# Main.net
KiCad netlist of a schematic drawn in Altium Designer
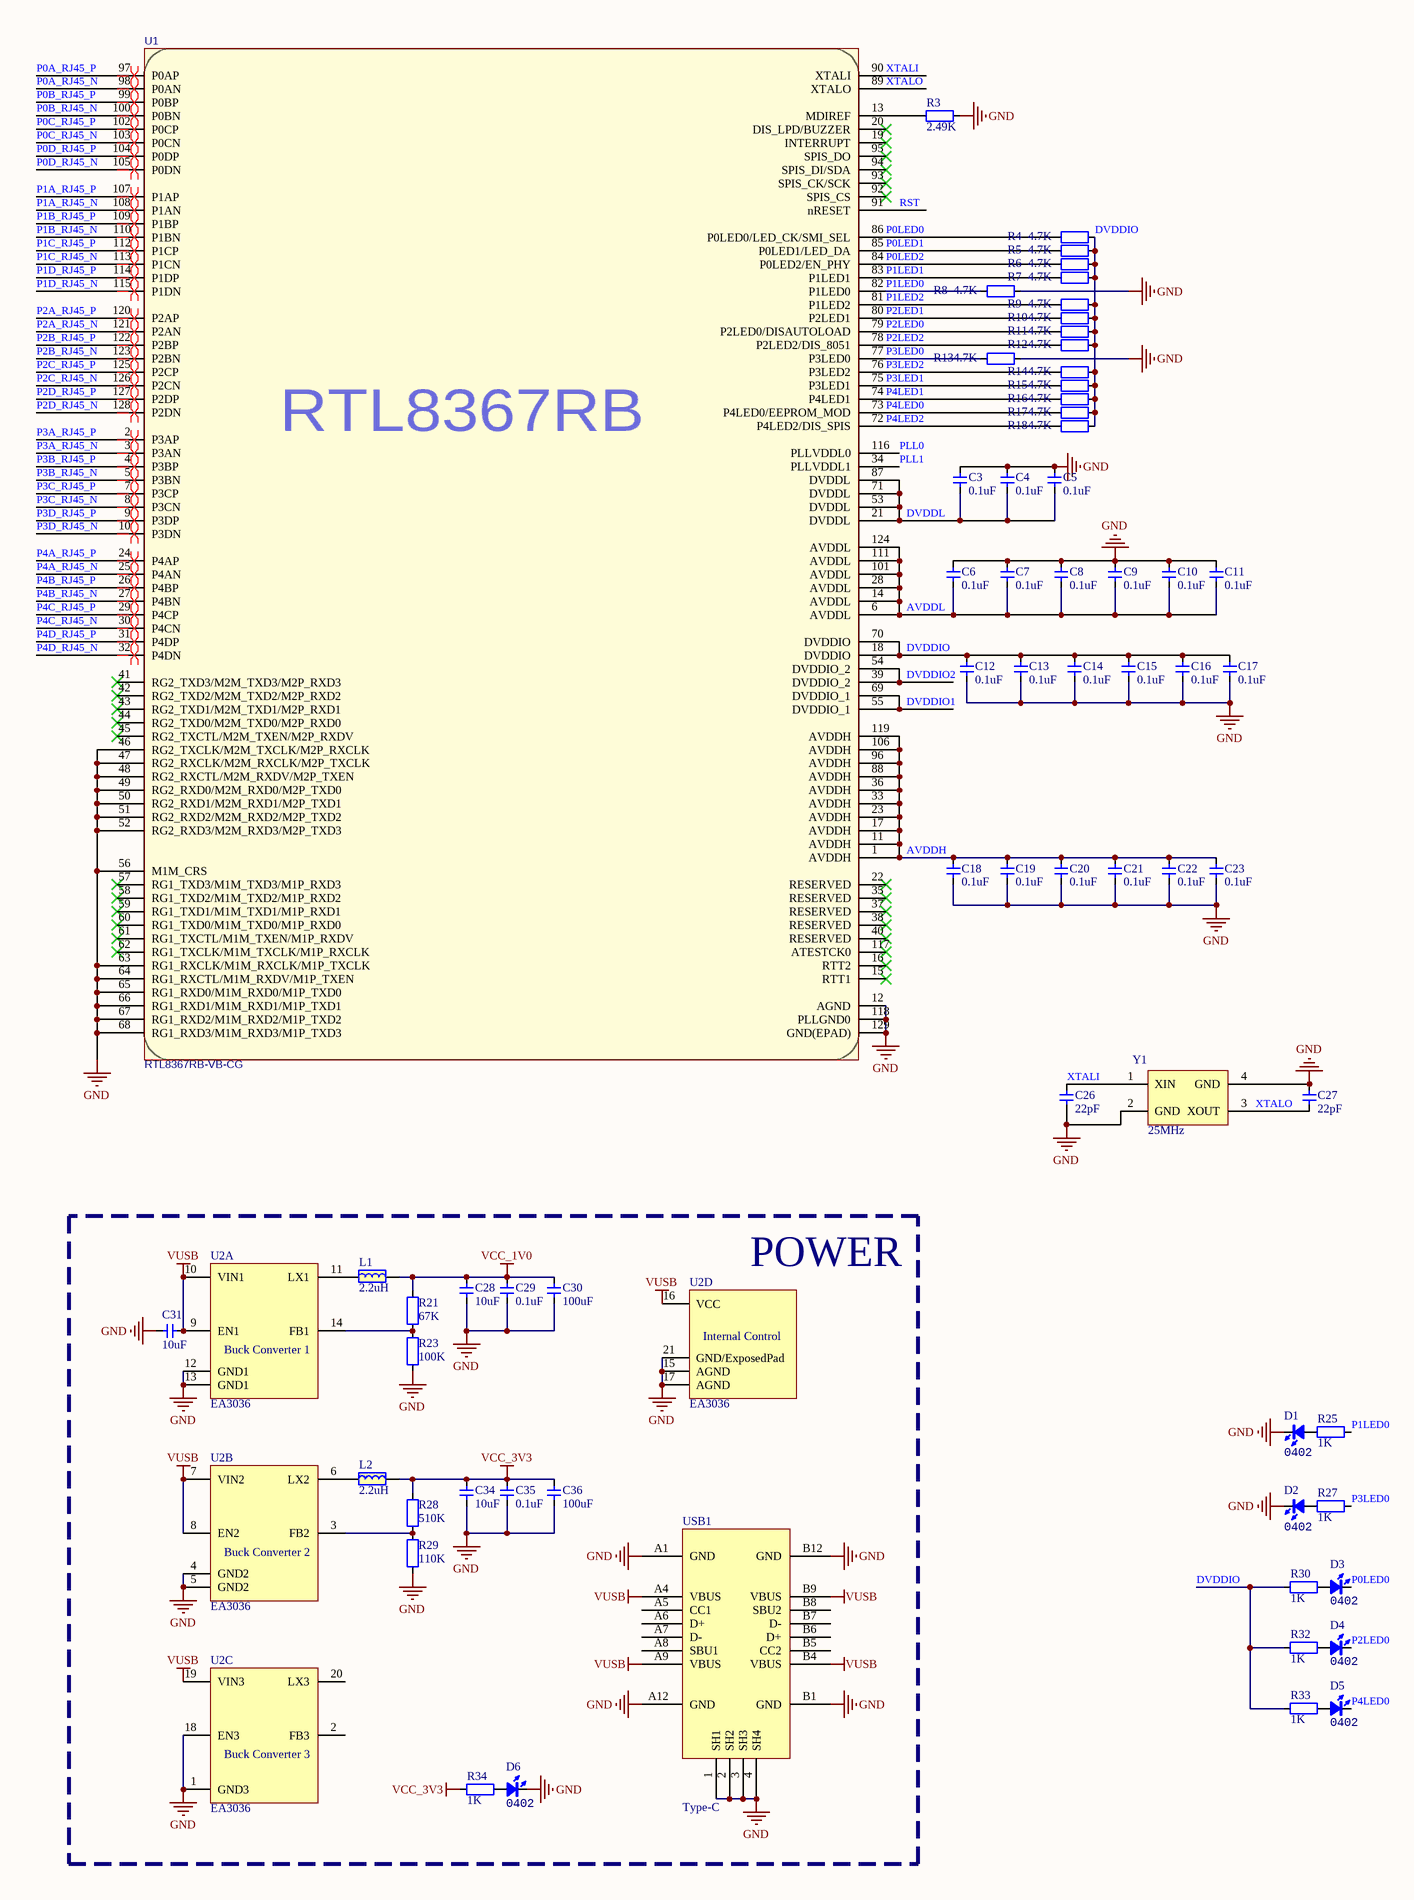
[diagram p0: Main.SchDoc, left]
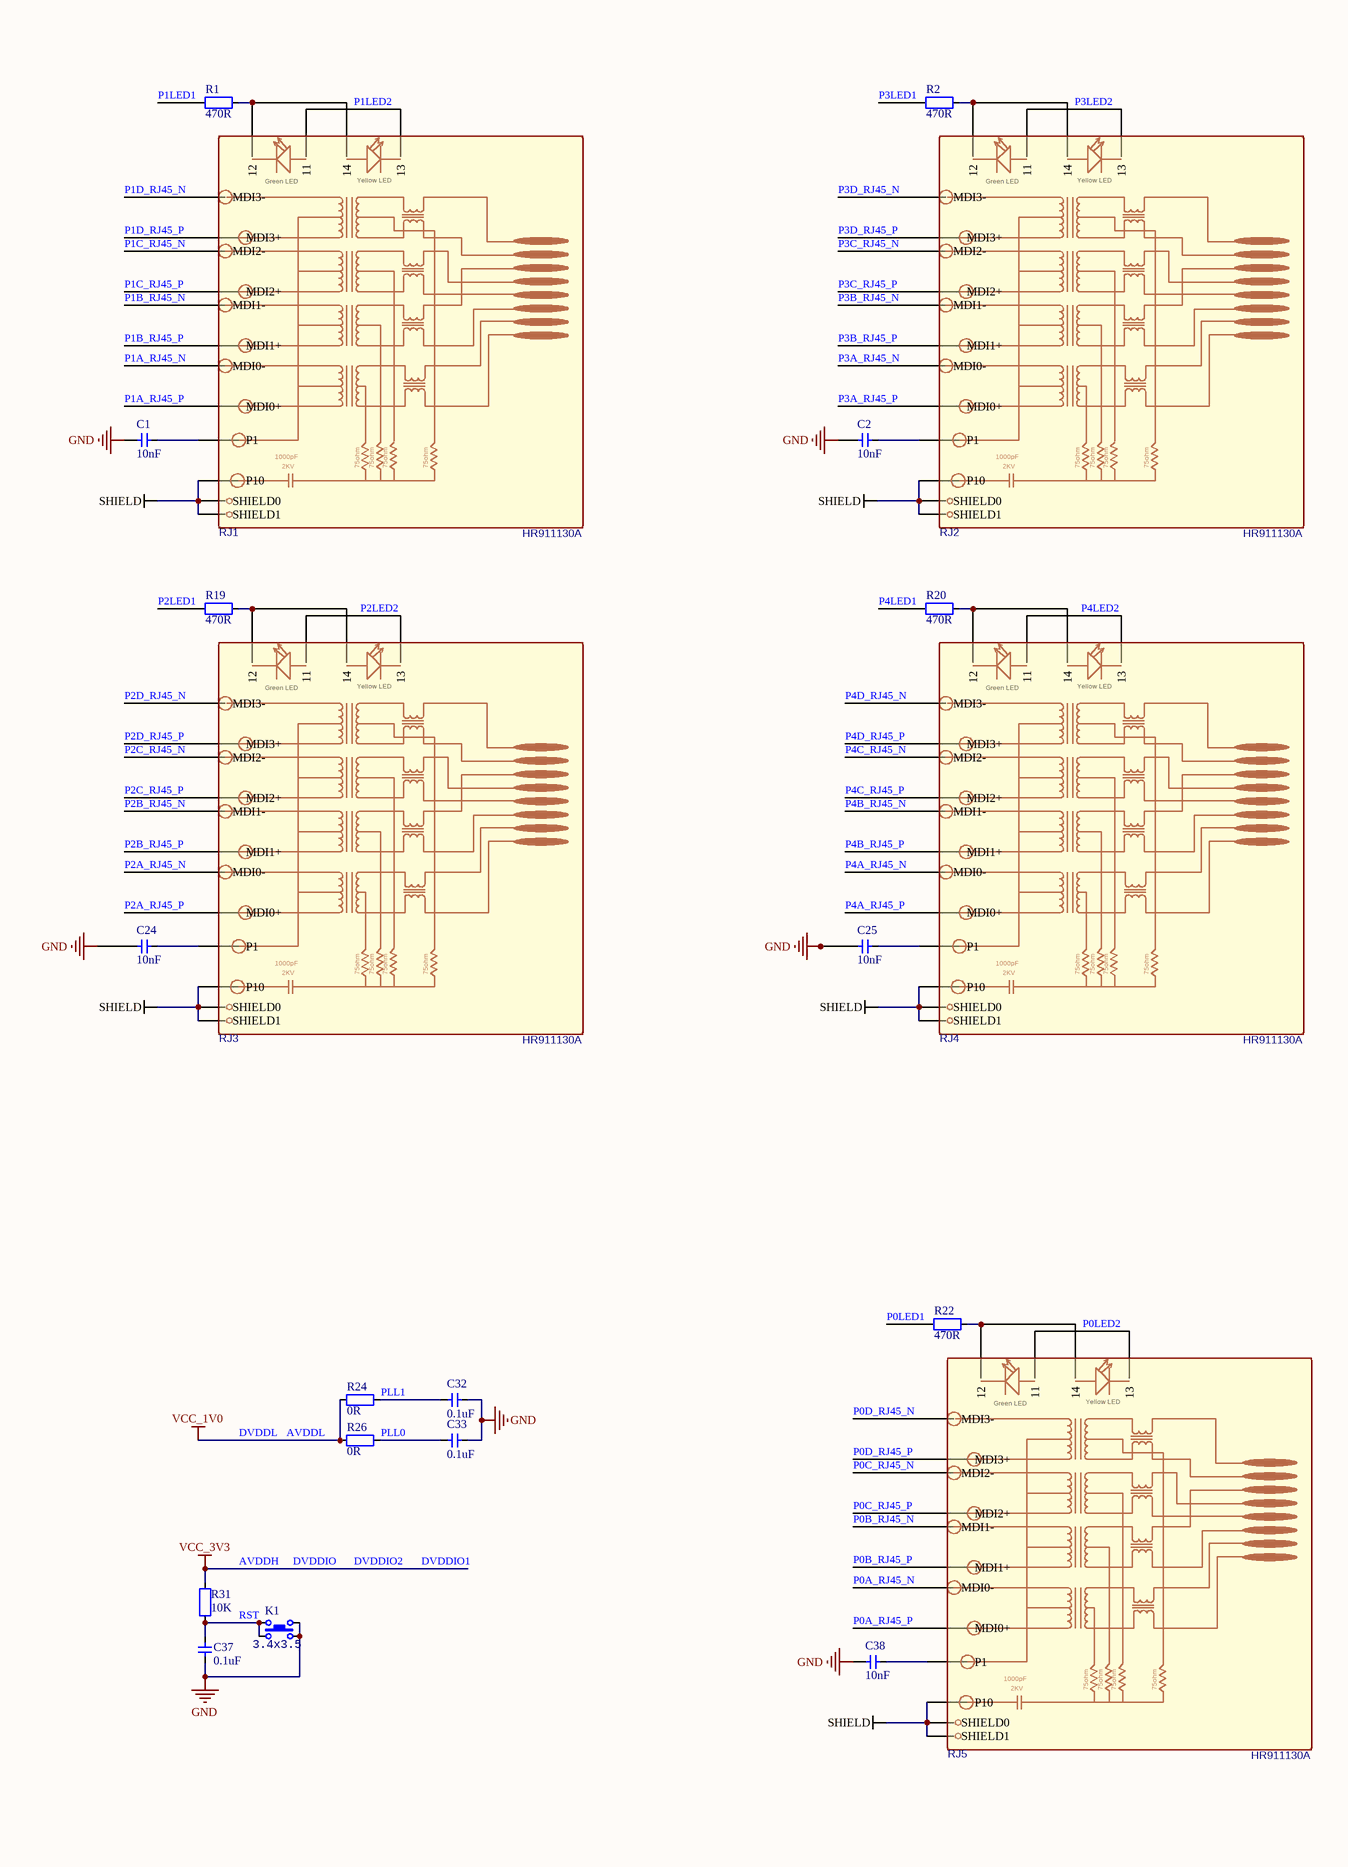
[diagram p1: Main.SchDoc, right]

(export (version "E")
  (design (tool "Eeschema 10.0.6"))
  (components
    (comp (ref "C1")
      (value "10nF")
      (footprint "CAP_0402")
      (description "Capacitor")
      (libsource (lib "MyPcbLib") (part "电容-0402"))
    )
    (comp (ref "C2")
      (value "10nF")
      (footprint "CAP_0402")
      (description "Capacitor")
      (libsource (lib "MyPcbLib") (part "电容-0402"))
    )
    (comp (ref "C3")
      (value "0.1uF")
      (footprint "CAP_0402")
      (description "Capacitor")
      (libsource (lib "MyPcbLib") (part "电容-0402"))
    )
    (comp (ref "C4")
      (value "0.1uF")
      (footprint "CAP_0402")
      (description "Capacitor")
      (libsource (lib "MyPcbLib") (part "电容-0402"))
    )
    (comp (ref "C5")
      (value "0.1uF")
      (footprint "CAP_0402")
      (description "Capacitor")
      (libsource (lib "MyPcbLib") (part "电容-0402"))
    )
    (comp (ref "C6")
      (value "0.1uF")
      (footprint "CAP_0402")
      (description "Capacitor")
      (libsource (lib "MyPcbLib") (part "电容-0402"))
    )
    (comp (ref "C7")
      (value "0.1uF")
      (footprint "CAP_0402")
      (description "Capacitor")
      (libsource (lib "MyPcbLib") (part "电容-0402"))
    )
    (comp (ref "C8")
      (value "0.1uF")
      (footprint "CAP_0402")
      (description "Capacitor")
      (libsource (lib "MyPcbLib") (part "电容-0402"))
    )
    (comp (ref "C9")
      (value "0.1uF")
      (footprint "CAP_0402")
      (description "Capacitor")
      (libsource (lib "MyPcbLib") (part "电容-0402"))
    )
    (comp (ref "C10")
      (value "0.1uF")
      (footprint "CAP_0402")
      (description "Capacitor")
      (libsource (lib "MyPcbLib") (part "电容-0402"))
    )
    (comp (ref "C11")
      (value "0.1uF")
      (footprint "CAP_0402")
      (description "Capacitor")
      (libsource (lib "MyPcbLib") (part "电容-0402"))
    )
    (comp (ref "C12")
      (value "0.1uF")
      (footprint "CAP_0402")
      (description "Capacitor")
      (libsource (lib "MyPcbLib") (part "电容-0402"))
    )
    (comp (ref "C13")
      (value "0.1uF")
      (footprint "CAP_0402")
      (description "Capacitor")
      (libsource (lib "MyPcbLib") (part "电容-0402"))
    )
    (comp (ref "C14")
      (value "0.1uF")
      (footprint "CAP_0402")
      (description "Capacitor")
      (libsource (lib "MyPcbLib") (part "电容-0402"))
    )
    (comp (ref "C15")
      (value "0.1uF")
      (footprint "CAP_0402")
      (description "Capacitor")
      (libsource (lib "MyPcbLib") (part "电容-0402"))
    )
    (comp (ref "C16")
      (value "0.1uF")
      (footprint "CAP_0402")
      (description "Capacitor")
      (libsource (lib "MyPcbLib") (part "电容-0402"))
    )
    (comp (ref "C17")
      (value "0.1uF")
      (footprint "CAP_0402")
      (description "Capacitor")
      (libsource (lib "MyPcbLib") (part "电容-0402"))
    )
    (comp (ref "C18")
      (value "0.1uF")
      (footprint "CAP_0402")
      (description "Capacitor")
      (libsource (lib "MyPcbLib") (part "电容-0402"))
    )
    (comp (ref "C19")
      (value "0.1uF")
      (footprint "CAP_0402")
      (description "Capacitor")
      (libsource (lib "MyPcbLib") (part "电容-0402"))
    )
    (comp (ref "C20")
      (value "0.1uF")
      (footprint "CAP_0402")
      (description "Capacitor")
      (libsource (lib "MyPcbLib") (part "电容-0402"))
    )
    (comp (ref "C21")
      (value "0.1uF")
      (footprint "CAP_0402")
      (description "Capacitor")
      (libsource (lib "MyPcbLib") (part "电容-0402"))
    )
    (comp (ref "C22")
      (value "0.1uF")
      (footprint "CAP_0402")
      (description "Capacitor")
      (libsource (lib "MyPcbLib") (part "电容-0402"))
    )
    (comp (ref "C23")
      (value "0.1uF")
      (footprint "CAP_0402")
      (description "Capacitor")
      (libsource (lib "MyPcbLib") (part "电容-0402"))
    )
    (comp (ref "C24")
      (value "10nF")
      (footprint "CAP_0402")
      (description "Capacitor")
      (libsource (lib "MyPcbLib") (part "电容-0402"))
    )
    (comp (ref "C25")
      (value "10nF")
      (footprint "CAP_0402")
      (description "Capacitor")
      (libsource (lib "MyPcbLib") (part "电容-0402"))
    )
    (comp (ref "C26")
      (value "22pF")
      (footprint "CAP_0402")
      (description "Capacitor")
      (libsource (lib "MyPcbLib") (part "电容-0402"))
    )
    (comp (ref "C27")
      (value "22pF")
      (footprint "CAP_0402")
      (description "Capacitor")
      (libsource (lib "MyPcbLib") (part "电容-0402"))
    )
    (comp (ref "C28")
      (value "10uF")
      (footprint "CAP_0402")
      (description "Capacitor")
      (libsource (lib "MyPcbLib") (part "电容-0402"))
    )
    (comp (ref "C29")
      (value "0.1uF")
      (footprint "CAP_0402")
      (description "Capacitor")
      (libsource (lib "MyPcbLib") (part "电容-0402"))
    )
    (comp (ref "C30")
      (value "100uF")
      (footprint "1206-CAP")
      (description "Capacitor")
      (libsource (lib "MyPcbLib") (part "电容-1206"))
    )
    (comp (ref "C31")
      (value "10uF")
      (footprint "CAP_0402")
      (description "Capacitor")
      (libsource (lib "MyPcbLib") (part "电容-0402"))
    )
    (comp (ref "C32")
      (value "0.1uF")
      (footprint "CAP_0402")
      (description "Capacitor")
      (libsource (lib "MyPcbLib") (part "电容-0402"))
    )
    (comp (ref "C33")
      (value "0.1uF")
      (footprint "CAP_0402")
      (description "Capacitor")
      (libsource (lib "MyPcbLib") (part "电容-0402"))
    )
    (comp (ref "C34")
      (value "10uF")
      (footprint "CAP_0402")
      (description "Capacitor")
      (libsource (lib "MyPcbLib") (part "电容-0402"))
    )
    (comp (ref "C35")
      (value "0.1uF")
      (footprint "CAP_0402")
      (description "Capacitor")
      (libsource (lib "MyPcbLib") (part "电容-0402"))
    )
    (comp (ref "C36")
      (value "100uF")
      (footprint "1206-CAP")
      (description "Capacitor")
      (libsource (lib "MyPcbLib") (part "电容-1206"))
    )
    (comp (ref "C37")
      (value "0.1uF")
      (footprint "CAP_0402")
      (description "Capacitor")
      (libsource (lib "MyPcbLib") (part "电容-0402"))
    )
    (comp (ref "C38")
      (value "10nF")
      (footprint "CAP_0402")
      (description "Capacitor")
      (libsource (lib "MyPcbLib") (part "电容-0402"))
    )
    (comp (ref "D1")
      (value "color?")
      (footprint "LED_0402_RED")
      (description "LED")
      (fields (field (name "TYPE") "0402"))
      (libsource (lib "KitSprout") (part "LED_0402"))
    )
    (comp (ref "D2")
      (value "color?")
      (footprint "LED_0402_RED")
      (description "LED")
      (fields (field (name "TYPE") "0402"))
      (libsource (lib "KitSprout") (part "LED_0402"))
    )
    (comp (ref "D3")
      (value "color?")
      (footprint "LED_0402_RED")
      (description "LED")
      (fields (field (name "TYPE") "0402"))
      (libsource (lib "") (part "LED_0402_1"))
    )
    (comp (ref "D4")
      (value "color?")
      (footprint "LED_0402_RED")
      (description "LED")
      (fields (field (name "TYPE") "0402"))
      (libsource (lib "") (part "LED_0402_1"))
    )
    (comp (ref "D5")
      (value "color?")
      (footprint "LED_0402_RED")
      (description "LED")
      (fields (field (name "TYPE") "0402"))
      (libsource (lib "") (part "LED_0402_1"))
    )
    (comp (ref "D6")
      (value "color?")
      (footprint "LED_0402_RED")
      (description "LED")
      (fields (field (name "TYPE") "0402"))
      (libsource (lib "") (part "LED_0402_1"))
    )
    (comp (ref "K1")
      (value "3.4x3.5")
      (footprint "ButtonTACT_3.5*3.55_90")
      (description "Button")
      (fields (field (name "Comment") "TACT 4P"))
      (libsource (lib "KitSprout") (part "ButtonTACT"))
    )
    (comp (ref "L1")
      (value "2.2uH")
      (footprint "2520-L")
      (description "磁珠")
      (libsource (lib "MyPcbLib") (part "电感-2520"))
    )
    (comp (ref "L2")
      (value "2.2uH")
      (footprint "2520-L")
      (description "磁珠")
      (libsource (lib "MyPcbLib") (part "电感-2520"))
    )
    (comp (ref "R1")
      (value "470R")
      (footprint "RES_0402")
      (description "Resistor")
      (libsource (lib "MyPcbLib") (part "电阻-0402"))
    )
    (comp (ref "R2")
      (value "470R")
      (footprint "RES_0402")
      (description "Resistor")
      (libsource (lib "MyPcbLib") (part "电阻-0402"))
    )
    (comp (ref "R3")
      (value "2.49K")
      (footprint "RES_0402")
      (description "Resistor")
      (libsource (lib "MyPcbLib") (part "电阻-0402"))
    )
    (comp (ref "R4")
      (value "4.7K")
      (footprint "RES_0402")
      (description "Resistor")
      (libsource (lib "MyPcbLib") (part "电阻-0402"))
    )
    (comp (ref "R5")
      (value "4.7K")
      (footprint "RES_0402")
      (description "Resistor")
      (libsource (lib "MyPcbLib") (part "电阻-0402"))
    )
    (comp (ref "R6")
      (value "4.7K")
      (footprint "RES_0402")
      (description "Resistor")
      (libsource (lib "MyPcbLib") (part "电阻-0402"))
    )
    (comp (ref "R7")
      (value "4.7K")
      (footprint "RES_0402")
      (description "Resistor")
      (libsource (lib "MyPcbLib") (part "电阻-0402"))
    )
    (comp (ref "R8")
      (value "4.7K")
      (footprint "RES_0402")
      (description "Resistor")
      (libsource (lib "MyPcbLib") (part "电阻-0402"))
    )
    (comp (ref "R9")
      (value "4.7K")
      (footprint "RES_0402")
      (description "Resistor")
      (libsource (lib "MyPcbLib") (part "电阻-0402"))
    )
    (comp (ref "R10")
      (value "4.7K")
      (footprint "RES_0402")
      (description "Resistor")
      (libsource (lib "MyPcbLib") (part "电阻-0402"))
    )
    (comp (ref "R11")
      (value "4.7K")
      (footprint "RES_0402")
      (description "Resistor")
      (libsource (lib "MyPcbLib") (part "电阻-0402"))
    )
    (comp (ref "R12")
      (value "4.7K")
      (footprint "RES_0402")
      (description "Resistor")
      (libsource (lib "MyPcbLib") (part "电阻-0402"))
    )
    (comp (ref "R13")
      (value "4.7K")
      (footprint "RES_0402")
      (description "Resistor")
      (libsource (lib "MyPcbLib") (part "电阻-0402"))
    )
    (comp (ref "R14")
      (value "4.7K")
      (footprint "RES_0402")
      (description "Resistor")
      (libsource (lib "MyPcbLib") (part "电阻-0402"))
    )
    (comp (ref "R15")
      (value "4.7K")
      (footprint "RES_0402")
      (description "Resistor")
      (libsource (lib "MyPcbLib") (part "电阻-0402"))
    )
    (comp (ref "R16")
      (value "4.7K")
      (footprint "RES_0402")
      (description "Resistor")
      (libsource (lib "MyPcbLib") (part "电阻-0402"))
    )
    (comp (ref "R17")
      (value "4.7K")
      (footprint "RES_0402")
      (description "Resistor")
      (libsource (lib "MyPcbLib") (part "电阻-0402"))
    )
    (comp (ref "R18")
      (value "4.7K")
      (footprint "RES_0402")
      (description "Resistor")
      (libsource (lib "MyPcbLib") (part "电阻-0402"))
    )
    (comp (ref "R19")
      (value "470R")
      (footprint "RES_0402")
      (description "Resistor")
      (libsource (lib "MyPcbLib") (part "电阻-0402"))
    )
    (comp (ref "R20")
      (value "470R")
      (footprint "RES_0402")
      (description "Resistor")
      (libsource (lib "MyPcbLib") (part "电阻-0402"))
    )
    (comp (ref "R21")
      (value "67K")
      (footprint "RES_0402")
      (description "Resistor")
      (libsource (lib "") (part "电阻-0402_2"))
    )
    (comp (ref "R22")
      (value "470R")
      (footprint "RES_0402")
      (description "Resistor")
      (libsource (lib "MyPcbLib") (part "电阻-0402"))
    )
    (comp (ref "R23")
      (value "100K")
      (footprint "RES_0402")
      (description "Resistor")
      (libsource (lib "") (part "电阻-0402_2"))
    )
    (comp (ref "R24")
      (value "0R")
      (footprint "RES_0402")
      (description "Resistor")
      (libsource (lib "") (part "电阻-0402_1"))
    )
    (comp (ref "R25")
      (value "1K")
      (footprint "RES_0402")
      (description "Resistor")
      (libsource (lib "") (part "电阻-0402_1"))
    )
    (comp (ref "R26")
      (value "0R")
      (footprint "RES_0402")
      (description "Resistor")
      (libsource (lib "") (part "电阻-0402_1"))
    )
    (comp (ref "R27")
      (value "1K")
      (footprint "RES_0402")
      (description "Resistor")
      (libsource (lib "") (part "电阻-0402_1"))
    )
    (comp (ref "R28")
      (value "510K")
      (footprint "RES_0402")
      (description "Resistor")
      (libsource (lib "") (part "电阻-0402_2"))
    )
    (comp (ref "R29")
      (value "110K")
      (footprint "RES_0402")
      (description "Resistor")
      (libsource (lib "") (part "电阻-0402_2"))
    )
    (comp (ref "R30")
      (value "1K")
      (footprint "RES_0402")
      (description "Resistor")
      (libsource (lib "MyPcbLib") (part "电阻-0402"))
    )
    (comp (ref "R31")
      (value "10K")
      (footprint "RES_0402")
      (description "Resistor")
      (libsource (lib "") (part "电阻-0402_2"))
    )
    (comp (ref "R32")
      (value "1K")
      (footprint "RES_0402")
      (description "Resistor")
      (libsource (lib "MyPcbLib") (part "电阻-0402"))
    )
    (comp (ref "R33")
      (value "1K")
      (footprint "RES_0402")
      (description "Resistor")
      (libsource (lib "MyPcbLib") (part "电阻-0402"))
    )
    (comp (ref "R34")
      (value "1K")
      (footprint "RES_0402")
      (description "Resistor")
      (libsource (lib "MyPcbLib") (part "电阻-0402"))
    )
    (comp (ref "RJ1")
      (value "HR911130A")
      (footprint "RJ45-TH_HR911130A")
      (fields (field (name "BOM_SUPPLIER PART") "C54408"))
      (libsource (lib "MyPcbLib") (part "HR911130A"))
    )
    (comp (ref "RJ2")
      (value "HR911130A")
      (footprint "RJ45-TH_HR911130A")
      (fields (field (name "BOM_SUPPLIER PART") "C54408"))
      (libsource (lib "MyPcbLib") (part "HR911130A"))
    )
    (comp (ref "RJ3")
      (value "HR911130A")
      (footprint "RJ45-TH_HR911130A")
      (fields (field (name "BOM_SUPPLIER PART") "C54408"))
      (libsource (lib "MyPcbLib") (part "HR911130A"))
    )
    (comp (ref "RJ4")
      (value "HR911130A")
      (footprint "RJ45-TH_HR911130A")
      (fields (field (name "BOM_SUPPLIER PART") "C54408"))
      (libsource (lib "MyPcbLib") (part "HR911130A"))
    )
    (comp (ref "RJ5")
      (value "HR911130A")
      (footprint "RJ45-TH_HR911130A")
      (fields (field (name "BOM_SUPPLIER PART") "C54408"))
      (libsource (lib "MyPcbLib") (part "HR911130A"))
    )
    (comp (ref "U1")
      (value "RTL8367RB-VB-CG")
      (footprint "LQFP-128")
      (fields (field (name "CONTRIBUTOR") "libc0607"))
      (libsource (lib "MyPcbLib") (part "RTL8367RB-VB-CG"))
    )
    (comp (ref "U2") (value "EA3036") (footprint "QFN-20") (libsource (lib "MyPcbLib") (part "EA3036")))
    (comp (ref "USB1")
      (value "Type-C")
      (footprint "Type-C-TOP")
      (libsource (lib "MyPcbLib") (part "USB-Type-C-TOP"))
    )
    (comp (ref "Y1")
      (value "25MHz")
      (footprint "晶振2520")
      (description "2520无源")
      (fields (field (name "MF") "ECS International") (field (name "MP") "ECS-3225S30-240-EN-TR"))
      (libsource (lib "MyPcbLib") (part "晶振-4Pin-无源"))
    )
  )
  (nets
    (net (code "1") (name "/P0A_RJ45_N") (class "Default")
      (node (ref "RJ5") (pin "P3") (pinfunction "MDI0-_P3") (pintype "passive"))
      (node (ref "U1") (pin "98") (pinfunction "P0AN_98") (pintype "passive"))
    )
    (net (code "2") (name "/P0A_RJ45_P") (class "Default")
      (node (ref "RJ5") (pin "P2") (pinfunction "MDI0+_P2") (pintype "passive"))
      (node (ref "U1") (pin "97") (pinfunction "P0AP_97") (pintype "passive"))
    )
    (net (code "3") (name "/P0B_RJ45_N") (class "Default")
      (node (ref "RJ5") (pin "P7") (pinfunction "MDI1-_P7") (pintype "passive"))
      (node (ref "U1") (pin "100") (pinfunction "P0BN_100") (pintype "passive"))
    )
    (net (code "4") (name "/P0B_RJ45_P") (class "Default")
      (node (ref "RJ5") (pin "P4") (pinfunction "MDI1+_P4") (pintype "passive"))
      (node (ref "U1") (pin "99") (pinfunction "P0BP_99") (pintype "passive"))
    )
    (net (code "5") (name "/P0C_RJ45_N") (class "Default")
      (node (ref "RJ5") (pin "P6") (pinfunction "MDI2-_P6") (pintype "passive"))
      (node (ref "U1") (pin "103") (pinfunction "P0CN_103") (pintype "passive"))
    )
    (net (code "6") (name "/P0C_RJ45_P") (class "Default")
      (node (ref "RJ5") (pin "P5") (pinfunction "MDI2+_P5") (pintype "passive"))
      (node (ref "U1") (pin "102") (pinfunction "P0CP_102") (pintype "passive"))
    )
    (net (code "7") (name "/P0D_RJ45_N") (class "Default")
      (node (ref "RJ5") (pin "P9") (pinfunction "MDI3-_P9") (pintype "passive"))
      (node (ref "U1") (pin "105") (pinfunction "P0DN_105") (pintype "passive"))
    )
    (net (code "8") (name "/P0D_RJ45_P") (class "Default")
      (node (ref "RJ5") (pin "P8") (pinfunction "MDI3+_P8") (pintype "passive"))
      (node (ref "U1") (pin "104") (pinfunction "P0DP_104") (pintype "passive"))
    )
    (net (code "9") (name "/P0LED0") (class "Default")
      (node (ref "D3") (pin "2") (pinfunction "K_2") (pintype "passive"))
      (node (ref "R4") (pin "1") (pinfunction "1_1") (pintype "passive"))
      (node (ref "U1") (pin "86") (pinfunction "P0LED0/LED_CK/SMI_SEL_86") (pintype "passive"))
    )
    (net (code "10") (name "/P0LED1") (class "Default")
      (node (ref "R22") (pin "1") (pinfunction "1_1") (pintype "passive"))
      (node (ref "R5") (pin "1") (pinfunction "1_1") (pintype "passive"))
      (node (ref "U1") (pin "85") (pinfunction "P0LED1/LED_DA_85") (pintype "passive"))
    )
    (net (code "11") (name "/P0LED2") (class "Default")
      (node (ref "R6") (pin "1") (pinfunction "1_1") (pintype "passive"))
      (node (ref "RJ5") (pin "11") (pinfunction "11_11") (pintype "passive"))
      (node (ref "RJ5") (pin "13") (pinfunction "13_13") (pintype "passive"))
      (node (ref "U1") (pin "84") (pinfunction "P0LED2/EN_PHY_84") (pintype "passive"))
    )
    (net (code "12") (name "/P1A_RJ45_N") (class "Default")
      (node (ref "RJ1") (pin "P3") (pinfunction "MDI0-_P3") (pintype "passive"))
      (node (ref "U1") (pin "108") (pinfunction "P1AN_108") (pintype "passive"))
    )
    (net (code "13") (name "/P1A_RJ45_P") (class "Default")
      (node (ref "RJ1") (pin "P2") (pinfunction "MDI0+_P2") (pintype "passive"))
      (node (ref "U1") (pin "107") (pinfunction "P1AP_107") (pintype "passive"))
    )
    (net (code "14") (name "/P1B_RJ45_N") (class "Default")
      (node (ref "RJ1") (pin "P7") (pinfunction "MDI1-_P7") (pintype "passive"))
      (node (ref "U1") (pin "110") (pinfunction "P1BN_110") (pintype "passive"))
    )
    (net (code "15") (name "/P1B_RJ45_P") (class "Default")
      (node (ref "RJ1") (pin "P4") (pinfunction "MDI1+_P4") (pintype "passive"))
      (node (ref "U1") (pin "109") (pinfunction "P1BP_109") (pintype "passive"))
    )
    (net (code "16") (name "/P1C_RJ45_N") (class "Default")
      (node (ref "RJ1") (pin "P6") (pinfunction "MDI2-_P6") (pintype "passive"))
      (node (ref "U1") (pin "113") (pinfunction "P1CN_113") (pintype "passive"))
    )
    (net (code "17") (name "/P1C_RJ45_P") (class "Default")
      (node (ref "RJ1") (pin "P5") (pinfunction "MDI2+_P5") (pintype "passive"))
      (node (ref "U1") (pin "112") (pinfunction "P1CP_112") (pintype "passive"))
    )
    (net (code "18") (name "/P1D_RJ45_N") (class "Default")
      (node (ref "RJ1") (pin "P9") (pinfunction "MDI3-_P9") (pintype "passive"))
      (node (ref "U1") (pin "115") (pinfunction "P1DN_115") (pintype "passive"))
    )
    (net (code "19") (name "/P1D_RJ45_P") (class "Default")
      (node (ref "RJ1") (pin "P8") (pinfunction "MDI3+_P8") (pintype "passive"))
      (node (ref "U1") (pin "114") (pinfunction "P1DP_114") (pintype "passive"))
    )
    (net (code "20") (name "/P1LED0") (class "Default")
      (node (ref "R25") (pin "1") (pinfunction "1_1") (pintype "passive"))
      (node (ref "R8") (pin "1") (pinfunction "1_1") (pintype "passive"))
      (node (ref "U1") (pin "82") (pinfunction "P1LED0_82") (pintype "passive"))
    )
    (net (code "21") (name "/P1LED1") (class "Default")
      (node (ref "R1") (pin "1") (pinfunction "1_1") (pintype "passive"))
      (node (ref "R7") (pin "1") (pinfunction "1_1") (pintype "passive"))
      (node (ref "U1") (pin "83") (pinfunction "P1LED1_83") (pintype "passive"))
    )
    (net (code "22") (name "/P1LED2") (class "Default")
      (node (ref "R9") (pin "1") (pinfunction "1_1") (pintype "passive"))
      (node (ref "RJ1") (pin "11") (pinfunction "11_11") (pintype "passive"))
      (node (ref "RJ1") (pin "13") (pinfunction "13_13") (pintype "passive"))
      (node (ref "U1") (pin "81") (pinfunction "P1LED2_81") (pintype "passive"))
    )
    (net (code "23") (name "/P2A_RJ45_N") (class "Default")
      (node (ref "RJ3") (pin "P3") (pinfunction "MDI0-_P3") (pintype "passive"))
      (node (ref "U1") (pin "121") (pinfunction "P2AN_121") (pintype "passive"))
    )
    (net (code "24") (name "/P2A_RJ45_P") (class "Default")
      (node (ref "RJ3") (pin "P2") (pinfunction "MDI0+_P2") (pintype "passive"))
      (node (ref "U1") (pin "120") (pinfunction "P2AP_120") (pintype "passive"))
    )
    (net (code "25") (name "/P2B_RJ45_N") (class "Default")
      (node (ref "RJ3") (pin "P7") (pinfunction "MDI1-_P7") (pintype "passive"))
      (node (ref "U1") (pin "123") (pinfunction "P2BN_123") (pintype "passive"))
    )
    (net (code "26") (name "/P2B_RJ45_P") (class "Default")
      (node (ref "RJ3") (pin "P4") (pinfunction "MDI1+_P4") (pintype "passive"))
      (node (ref "U1") (pin "122") (pinfunction "P2BP_122") (pintype "passive"))
    )
    (net (code "27") (name "/P2C_RJ45_N") (class "Default")
      (node (ref "RJ3") (pin "P6") (pinfunction "MDI2-_P6") (pintype "passive"))
      (node (ref "U1") (pin "126") (pinfunction "P2CN_126") (pintype "passive"))
    )
    (net (code "28") (name "/P2C_RJ45_P") (class "Default")
      (node (ref "RJ3") (pin "P5") (pinfunction "MDI2+_P5") (pintype "passive"))
      (node (ref "U1") (pin "125") (pinfunction "P2CP_125") (pintype "passive"))
    )
    (net (code "29") (name "/P2D_RJ45_N") (class "Default")
      (node (ref "RJ3") (pin "P9") (pinfunction "MDI3-_P9") (pintype "passive"))
      (node (ref "U1") (pin "128") (pinfunction "P2DN_128") (pintype "passive"))
    )
    (net (code "30") (name "/P2D_RJ45_P") (class "Default")
      (node (ref "RJ3") (pin "P8") (pinfunction "MDI3+_P8") (pintype "passive"))
      (node (ref "U1") (pin "127") (pinfunction "P2DP_127") (pintype "passive"))
    )
    (net (code "31") (name "/P2LED0") (class "Default")
      (node (ref "D4") (pin "2") (pinfunction "K_2") (pintype "passive"))
      (node (ref "R11") (pin "1") (pinfunction "1_1") (pintype "passive"))
      (node (ref "U1") (pin "79") (pinfunction "P2LED0/DISAUTOLOAD_79") (pintype "passive"))
    )
    (net (code "32") (name "/P2LED1") (class "Default")
      (node (ref "R10") (pin "1") (pinfunction "1_1") (pintype "passive"))
      (node (ref "R19") (pin "1") (pinfunction "1_1") (pintype "passive"))
      (node (ref "U1") (pin "80") (pinfunction "P2LED1_80") (pintype "passive"))
    )
    (net (code "33") (name "/P2LED2") (class "Default")
      (node (ref "R12") (pin "1") (pinfunction "1_1") (pintype "passive"))
      (node (ref "RJ3") (pin "11") (pinfunction "11_11") (pintype "passive"))
      (node (ref "RJ3") (pin "13") (pinfunction "13_13") (pintype "passive"))
      (node (ref "U1") (pin "78") (pinfunction "P2LED2/DIS_8051_78") (pintype "passive"))
    )
    (net (code "34") (name "/P3A_RJ45_N") (class "Default")
      (node (ref "RJ2") (pin "P3") (pinfunction "MDI0-_P3") (pintype "passive"))
      (node (ref "U1") (pin "3") (pinfunction "P3AN_3") (pintype "passive"))
    )
    (net (code "35") (name "/P3A_RJ45_P") (class "Default")
      (node (ref "RJ2") (pin "P2") (pinfunction "MDI0+_P2") (pintype "passive"))
      (node (ref "U1") (pin "2") (pinfunction "P3AP_2") (pintype "passive"))
    )
    (net (code "36") (name "/P3B_RJ45_N") (class "Default")
      (node (ref "RJ2") (pin "P7") (pinfunction "MDI1-_P7") (pintype "passive"))
      (node (ref "U1") (pin "5") (pinfunction "P3BN_5") (pintype "passive"))
    )
    (net (code "37") (name "/P3B_RJ45_P") (class "Default")
      (node (ref "RJ2") (pin "P4") (pinfunction "MDI1+_P4") (pintype "passive"))
      (node (ref "U1") (pin "4") (pinfunction "P3BP_4") (pintype "passive"))
    )
    (net (code "38") (name "/P3C_RJ45_N") (class "Default")
      (node (ref "RJ2") (pin "P6") (pinfunction "MDI2-_P6") (pintype "passive"))
      (node (ref "U1") (pin "8") (pinfunction "P3CN_8") (pintype "passive"))
    )
    (net (code "39") (name "/P3C_RJ45_P") (class "Default")
      (node (ref "RJ2") (pin "P5") (pinfunction "MDI2+_P5") (pintype "passive"))
      (node (ref "U1") (pin "7") (pinfunction "P3CP_7") (pintype "passive"))
    )
    (net (code "40") (name "/P3D_RJ45_N") (class "Default")
      (node (ref "RJ2") (pin "P9") (pinfunction "MDI3-_P9") (pintype "passive"))
      (node (ref "U1") (pin "10") (pinfunction "P3DN_10") (pintype "passive"))
    )
    (net (code "41") (name "/P3D_RJ45_P") (class "Default")
      (node (ref "RJ2") (pin "P8") (pinfunction "MDI3+_P8") (pintype "passive"))
      (node (ref "U1") (pin "9") (pinfunction "P3DP_9") (pintype "passive"))
    )
    (net (code "42") (name "/P3LED0") (class "Default")
      (node (ref "R13") (pin "1") (pinfunction "1_1") (pintype "passive"))
      (node (ref "R27") (pin "1") (pinfunction "1_1") (pintype "passive"))
      (node (ref "U1") (pin "77") (pinfunction "P3LED0_77") (pintype "passive"))
    )
    (net (code "43") (name "/P3LED1") (class "Default")
      (node (ref "R15") (pin "1") (pinfunction "1_1") (pintype "passive"))
      (node (ref "R2") (pin "1") (pinfunction "1_1") (pintype "passive"))
      (node (ref "U1") (pin "75") (pinfunction "P3LED1_75") (pintype "passive"))
    )
    (net (code "44") (name "/P3LED2") (class "Default")
      (node (ref "R14") (pin "1") (pinfunction "1_1") (pintype "passive"))
      (node (ref "RJ2") (pin "11") (pinfunction "11_11") (pintype "passive"))
      (node (ref "RJ2") (pin "13") (pinfunction "13_13") (pintype "passive"))
      (node (ref "U1") (pin "76") (pinfunction "P3LED2_76") (pintype "passive"))
    )
    (net (code "45") (name "/P4A_RJ45_N") (class "Default")
      (node (ref "RJ4") (pin "P3") (pinfunction "MDI0-_P3") (pintype "passive"))
      (node (ref "U1") (pin "25") (pinfunction "P4AN_25") (pintype "passive"))
    )
    (net (code "46") (name "/P4A_RJ45_P") (class "Default")
      (node (ref "RJ4") (pin "P2") (pinfunction "MDI0+_P2") (pintype "passive"))
      (node (ref "U1") (pin "24") (pinfunction "P4AP_24") (pintype "passive"))
    )
    (net (code "47") (name "/P4B_RJ45_N") (class "Default")
      (node (ref "RJ4") (pin "P7") (pinfunction "MDI1-_P7") (pintype "passive"))
      (node (ref "U1") (pin "27") (pinfunction "P4BN_27") (pintype "passive"))
    )
    (net (code "48") (name "/P4B_RJ45_P") (class "Default")
      (node (ref "RJ4") (pin "P4") (pinfunction "MDI1+_P4") (pintype "passive"))
      (node (ref "U1") (pin "26") (pinfunction "P4BP_26") (pintype "passive"))
    )
    (net (code "49") (name "/P4C_RJ45_N") (class "Default")
      (node (ref "RJ4") (pin "P6") (pinfunction "MDI2-_P6") (pintype "passive"))
      (node (ref "U1") (pin "30") (pinfunction "P4CN_30") (pintype "passive"))
    )
    (net (code "50") (name "/P4C_RJ45_P") (class "Default")
      (node (ref "RJ4") (pin "P5") (pinfunction "MDI2+_P5") (pintype "passive"))
      (node (ref "U1") (pin "29") (pinfunction "P4CP_29") (pintype "passive"))
    )
    (net (code "51") (name "/P4D_RJ45_N") (class "Default")
      (node (ref "RJ4") (pin "P9") (pinfunction "MDI3-_P9") (pintype "passive"))
      (node (ref "U1") (pin "32") (pinfunction "P4DN_32") (pintype "passive"))
    )
    (net (code "52") (name "/P4D_RJ45_P") (class "Default")
      (node (ref "RJ4") (pin "P8") (pinfunction "MDI3+_P8") (pintype "passive"))
      (node (ref "U1") (pin "31") (pinfunction "P4DP_31") (pintype "passive"))
    )
    (net (code "53") (name "/P4LED0") (class "Default")
      (node (ref "D5") (pin "2") (pinfunction "K_2") (pintype "passive"))
      (node (ref "R17") (pin "1") (pinfunction "1_1") (pintype "passive"))
      (node (ref "U1") (pin "73") (pinfunction "P4LED0/EEPROM_MOD_73") (pintype "passive"))
    )
    (net (code "54") (name "/P4LED1") (class "Default")
      (node (ref "R16") (pin "1") (pinfunction "1_1") (pintype "passive"))
      (node (ref "R20") (pin "1") (pinfunction "1_1") (pintype "passive"))
      (node (ref "U1") (pin "74") (pinfunction "P4LED1_74") (pintype "passive"))
    )
    (net (code "55") (name "/P4LED2") (class "Default")
      (node (ref "R18") (pin "1") (pinfunction "1_1") (pintype "passive"))
      (node (ref "RJ4") (pin "11") (pinfunction "11_11") (pintype "passive"))
      (node (ref "RJ4") (pin "13") (pinfunction "13_13") (pintype "passive"))
      (node (ref "U1") (pin "72") (pinfunction "P4LED2/DIS_SPIS_72") (pintype "passive"))
    )
    (net (code "56") (name "/PLL0") (class "Default")
      (node (ref "C33") (pin "1") (pinfunction "1_1") (pintype "passive"))
      (node (ref "R26") (pin "1") (pinfunction "1_1") (pintype "passive"))
      (node (ref "U1") (pin "116") (pinfunction "PLLVDDL0_116") (pintype "passive"))
    )
    (net (code "57") (name "/PLL1") (class "Default")
      (node (ref "C32") (pin "1") (pinfunction "1_1") (pintype "passive"))
      (node (ref "R24") (pin "1") (pinfunction "1_1") (pintype "passive"))
      (node (ref "U1") (pin "34") (pinfunction "PLLVDDL1_34") (pintype "passive"))
    )
    (net (code "58") (name "/RST") (class "Default")
      (node (ref "C37") (pin "1") (pinfunction "1_1") (pintype "passive"))
      (node (ref "K1") (pin "1") (pinfunction "1_1") (pintype "passive"))
      (node (ref "K1") (pin "3") (pinfunction "3_3") (pintype "passive"))
      (node (ref "R31") (pin "1") (pinfunction "1_1") (pintype "passive"))
      (node (ref "U1") (pin "91") (pinfunction "nRESET_91") (pintype "passive"))
    )
    (net (code "59") (name "/XTALI") (class "Default")
      (node (ref "C26") (pin "2") (pinfunction "2_2") (pintype "passive"))
      (node (ref "U1") (pin "90") (pinfunction "XTALI_90") (pintype "passive"))
      (node (ref "Y1") (pin "1") (pinfunction "XIN_1") (pintype "passive"))
    )
    (net (code "60") (name "/XTALO") (class "Default")
      (node (ref "C27") (pin "2") (pinfunction "2_2") (pintype "passive"))
      (node (ref "U1") (pin "89") (pinfunction "XTALO_89") (pintype "passive"))
      (node (ref "Y1") (pin "3") (pinfunction "XOUT_3") (pintype "passive"))
    )
    (net (code "61") (name "GND") (class "Default")
      (node (ref "C1") (pin "1") (pinfunction "1_1") (pintype "passive"))
      (node (ref "C10") (pin "1") (pinfunction "1_1") (pintype "passive"))
      (node (ref "C11") (pin "1") (pinfunction "1_1") (pintype "passive"))
      (node (ref "C12") (pin "2") (pinfunction "2_2") (pintype "passive"))
      (node (ref "C13") (pin "2") (pinfunction "2_2") (pintype "passive"))
      (node (ref "C14") (pin "2") (pinfunction "2_2") (pintype "passive"))
      (node (ref "C15") (pin "2") (pinfunction "2_2") (pintype "passive"))
      (node (ref "C16") (pin "2") (pinfunction "2_2") (pintype "passive"))
      (node (ref "C17") (pin "2") (pinfunction "2_2") (pintype "passive"))
      (node (ref "C18") (pin "2") (pinfunction "2_2") (pintype "passive"))
      (node (ref "C19") (pin "2") (pinfunction "2_2") (pintype "passive"))
      (node (ref "C2") (pin "1") (pinfunction "1_1") (pintype "passive"))
      (node (ref "C20") (pin "2") (pinfunction "2_2") (pintype "passive"))
      (node (ref "C21") (pin "2") (pinfunction "2_2") (pintype "passive"))
      (node (ref "C22") (pin "2") (pinfunction "2_2") (pintype "passive"))
      (node (ref "C23") (pin "2") (pinfunction "2_2") (pintype "passive"))
      (node (ref "C24") (pin "1") (pinfunction "1_1") (pintype "passive"))
      (node (ref "C25") (pin "1") (pinfunction "1_1") (pintype "passive"))
      (node (ref "C26") (pin "1") (pinfunction "1_1") (pintype "passive"))
      (node (ref "C27") (pin "1") (pinfunction "1_1") (pintype "passive"))
      (node (ref "C28") (pin "2") (pinfunction "2_2") (pintype "passive"))
      (node (ref "C29") (pin "2") (pinfunction "2_2") (pintype "passive"))
      (node (ref "C3") (pin "1") (pinfunction "1_1") (pintype "passive"))
      (node (ref "C30") (pin "1") (pinfunction "1_1") (pintype "passive"))
      (node (ref "C31") (pin "1") (pinfunction "1_1") (pintype "passive"))
      (node (ref "C32") (pin "2") (pinfunction "2_2") (pintype "passive"))
      (node (ref "C33") (pin "2") (pinfunction "2_2") (pintype "passive"))
      (node (ref "C34") (pin "2") (pinfunction "2_2") (pintype "passive"))
      (node (ref "C35") (pin "2") (pinfunction "2_2") (pintype "passive"))
      (node (ref "C36") (pin "1") (pinfunction "1_1") (pintype "passive"))
      (node (ref "C37") (pin "2") (pinfunction "2_2") (pintype "passive"))
      (node (ref "C38") (pin "1") (pinfunction "1_1") (pintype "passive"))
      (node (ref "C4") (pin "1") (pinfunction "1_1") (pintype "passive"))
      (node (ref "C5") (pin "1") (pinfunction "1_1") (pintype "passive"))
      (node (ref "C6") (pin "1") (pinfunction "1_1") (pintype "passive"))
      (node (ref "C7") (pin "1") (pinfunction "1_1") (pintype "passive"))
      (node (ref "C8") (pin "1") (pinfunction "1_1") (pintype "passive"))
      (node (ref "C9") (pin "1") (pinfunction "1_1") (pintype "passive"))
      (node (ref "D1") (pin "2") (pinfunction "K_2") (pintype "passive"))
      (node (ref "D2") (pin "2") (pinfunction "K_2") (pintype "passive"))
      (node (ref "D6") (pin "2") (pinfunction "K_2") (pintype "passive"))
      (node (ref "K1") (pin "2") (pinfunction "2_2") (pintype "passive"))
      (node (ref "K1") (pin "4") (pinfunction "4_4") (pintype "passive"))
      (node (ref "R13") (pin "2") (pinfunction "2_2") (pintype "passive"))
      (node (ref "R23") (pin "1") (pinfunction "1_1") (pintype "passive"))
      (node (ref "R29") (pin "1") (pinfunction "1_1") (pintype "passive"))
      (node (ref "R3") (pin "2") (pinfunction "2_2") (pintype "passive"))
      (node (ref "R8") (pin "2") (pinfunction "2_2") (pintype "passive"))
      (node (ref "U1") (pin "118") (pinfunction "PLLGND0_118") (pintype "passive"))
      (node (ref "U1") (pin "12") (pinfunction "AGND_12") (pintype "passive"))
      (node (ref "U1") (pin "129") (pinfunction "GND(EPAD)_129") (pintype "passive"))
      (node (ref "U1") (pin "46") (pinfunction "RG2_TXCLK/M2M_TXCLK/M2P_RXCLK_46") (pintype "passive"))
      (node (ref "U1") (pin "47") (pinfunction "RG2_RXCLK/M2M_RXCLK/M2P_TXCLK_47") (pintype "passive"))
      (node (ref "U1") (pin "48") (pinfunction "RG2_RXCTL/M2M_RXDV/M2P_TXEN_48") (pintype "passive"))
      (node (ref "U1") (pin "49") (pinfunction "RG2_RXD0/M2M_RXD0/M2P_TXD0_49") (pintype "passive"))
      (node (ref "U1") (pin "50") (pinfunction "RG2_RXD1/M2M_RXD1/M2P_TXD1_50") (pintype "passive"))
      (node (ref "U1") (pin "51") (pinfunction "RG2_RXD2/M2M_RXD2/M2P_TXD2_51") (pintype "passive"))
      (node (ref "U1") (pin "52") (pinfunction "RG2_RXD3/M2M_RXD3/M2P_TXD3_52") (pintype "passive"))
      (node (ref "U1") (pin "56") (pinfunction "M1M_CRS_56") (pintype "passive"))
      (node (ref "U1") (pin "63") (pinfunction "RG1_RXCLK/M1M_RXCLK/M1P_TXCLK_63") (pintype "passive"))
      (node (ref "U1") (pin "64") (pinfunction "RG1_RXCTL/M1M_RXDV/M1P_TXEN_64") (pintype "passive"))
      (node (ref "U1") (pin "65") (pinfunction "RG1_RXD0/M1M_RXD0/M1P_TXD0_65") (pintype "passive"))
      (node (ref "U1") (pin "66") (pinfunction "RG1_RXD1/M1M_RXD1/M1P_TXD1_66") (pintype "passive"))
      (node (ref "U1") (pin "67") (pinfunction "RG1_RXD2/M1M_RXD2/M1P_TXD2_67") (pintype "passive"))
      (node (ref "U1") (pin "68") (pinfunction "RG1_RXD3/M1M_RXD3/M1P_TXD3_68") (pintype "passive"))
      (node (ref "U2") (pin "1") (pinfunction "GND3_1") (pintype "power_in"))
      (node (ref "U2") (pin "12") (pinfunction "GND1_12") (pintype "power_in"))
      (node (ref "U2") (pin "13") (pinfunction "GND1_13") (pintype "power_in"))
      (node (ref "U2") (pin "15") (pinfunction "AGND_15") (pintype "power_in"))
      (node (ref "U2") (pin "17") (pinfunction "AGND_17") (pintype "power_in"))
      (node (ref "U2") (pin "18") (pinfunction "EN3_18") (pintype "passive"))
      (node (ref "U2") (pin "21") (pinfunction "GND/ExposedPad_21") (pintype "power_in"))
      (node (ref "U2") (pin "4") (pinfunction "GND2_4") (pintype "power_in"))
      (node (ref "U2") (pin "5") (pinfunction "GND2_5") (pintype "power_in"))
      (node (ref "USB1") (pin "1") (pinfunction "SH1_1") (pintype "passive"))
      (node (ref "USB1") (pin "2") (pinfunction "SH2_2") (pintype "passive"))
      (node (ref "USB1") (pin "3") (pinfunction "SH3_3") (pintype "passive"))
      (node (ref "USB1") (pin "4") (pinfunction "SH4_4") (pintype "passive"))
      (node (ref "USB1") (pin "A1") (pinfunction "GND_A1") (pintype "passive"))
      (node (ref "USB1") (pin "A12") (pinfunction "GND_A12") (pintype "passive"))
      (node (ref "USB1") (pin "B1") (pinfunction "GND_B1") (pintype "passive"))
      (node (ref "USB1") (pin "B12") (pinfunction "GND_B12") (pintype "passive"))
      (node (ref "Y1") (pin "2") (pinfunction "GND_2") (pintype "passive"))
      (node (ref "Y1") (pin "4") (pinfunction "GND_4") (pintype "passive"))
    )
    (net (code "62") (name "Net-(C1-Pad2)") (class "Default")
      (node (ref "C1") (pin "2") (pinfunction "2_2") (pintype "passive"))
      (node (ref "RJ1") (pin "P1") (pinfunction "P1_P1") (pintype "passive"))
    )
    (net (code "63") (name "Net-(C2-Pad2)") (class "Default")
      (node (ref "C2") (pin "2") (pinfunction "2_2") (pintype "passive"))
      (node (ref "RJ2") (pin "P1") (pinfunction "P1_P1") (pintype "passive"))
    )
    (net (code "64") (name "Net-(C24-Pad2)") (class "Default")
      (node (ref "C24") (pin "2") (pinfunction "2_2") (pintype "passive"))
      (node (ref "RJ3") (pin "P1") (pinfunction "P1_P1") (pintype "passive"))
    )
    (net (code "65") (name "Net-(C25-Pad2)") (class "Default")
      (node (ref "C25") (pin "2") (pinfunction "2_2") (pintype "passive"))
      (node (ref "RJ4") (pin "P1") (pinfunction "P1_P1") (pintype "passive"))
    )
    (net (code "66") (name "Net-(C38-Pad2)") (class "Default")
      (node (ref "C38") (pin "2") (pinfunction "2_2") (pintype "passive"))
      (node (ref "RJ5") (pin "P1") (pinfunction "P1_P1") (pintype "passive"))
    )
    (net (code "67") (name "Net-(D1-A)") (class "Default")
      (node (ref "D1") (pin "1") (pinfunction "A_1") (pintype "passive"))
      (node (ref "R25") (pin "2") (pinfunction "2_2") (pintype "passive"))
    )
    (net (code "68") (name "Net-(D2-A)") (class "Default")
      (node (ref "D2") (pin "1") (pinfunction "A_1") (pintype "passive"))
      (node (ref "R27") (pin "2") (pinfunction "2_2") (pintype "passive"))
    )
    (net (code "69") (name "Net-(D3-A)") (class "Default")
      (node (ref "D3") (pin "1") (pinfunction "A_1") (pintype "passive"))
      (node (ref "R30") (pin "2") (pinfunction "2_2") (pintype "passive"))
    )
    (net (code "70") (name "Net-(D4-A)") (class "Default")
      (node (ref "D4") (pin "1") (pinfunction "A_1") (pintype "passive"))
      (node (ref "R32") (pin "2") (pinfunction "2_2") (pintype "passive"))
    )
    (net (code "71") (name "Net-(D5-A)") (class "Default")
      (node (ref "D5") (pin "1") (pinfunction "A_1") (pintype "passive"))
      (node (ref "R33") (pin "2") (pinfunction "2_2") (pintype "passive"))
    )
    (net (code "72") (name "Net-(D6-A)") (class "Default")
      (node (ref "D6") (pin "1") (pinfunction "A_1") (pintype "passive"))
      (node (ref "R34") (pin "2") (pinfunction "2_2") (pintype "passive"))
    )
    (net (code "73") (name "Net-(R1-Pad2)") (class "Default")
      (node (ref "R1") (pin "2") (pinfunction "2_2") (pintype "passive"))
      (node (ref "RJ1") (pin "12") (pinfunction "12_12") (pintype "passive"))
      (node (ref "RJ1") (pin "14") (pinfunction "14_14") (pintype "passive"))
    )
    (net (code "74") (name "Net-(R2-Pad2)") (class "Default")
      (node (ref "R2") (pin "2") (pinfunction "2_2") (pintype "passive"))
      (node (ref "RJ2") (pin "12") (pinfunction "12_12") (pintype "passive"))
      (node (ref "RJ2") (pin "14") (pinfunction "14_14") (pintype "passive"))
    )
    (net (code "75") (name "Net-(R19-Pad2)") (class "Default")
      (node (ref "R19") (pin "2") (pinfunction "2_2") (pintype "passive"))
      (node (ref "RJ3") (pin "12") (pinfunction "12_12") (pintype "passive"))
      (node (ref "RJ3") (pin "14") (pinfunction "14_14") (pintype "passive"))
    )
    (net (code "76") (name "Net-(R20-Pad2)") (class "Default")
      (node (ref "R20") (pin "2") (pinfunction "2_2") (pintype "passive"))
      (node (ref "RJ4") (pin "12") (pinfunction "12_12") (pintype "passive"))
      (node (ref "RJ4") (pin "14") (pinfunction "14_14") (pintype "passive"))
    )
    (net (code "77") (name "Net-(R22-Pad2)") (class "Default")
      (node (ref "R22") (pin "2") (pinfunction "2_2") (pintype "passive"))
      (node (ref "RJ5") (pin "12") (pinfunction "12_12") (pintype "passive"))
      (node (ref "RJ5") (pin "14") (pinfunction "14_14") (pintype "passive"))
    )
    (net (code "78") (name "Net-(U1-MDIREF)") (class "Default")
      (node (ref "R3") (pin "1") (pinfunction "1_1") (pintype "passive"))
      (node (ref "U1") (pin "13") (pinfunction "MDIREF_13") (pintype "passive"))
    )
    (net (code "79") (name "Net-(U2A-FB1)") (class "Default")
      (node (ref "R21") (pin "1") (pinfunction "1_1") (pintype "passive"))
      (node (ref "R23") (pin "2") (pinfunction "2_2") (pintype "passive"))
      (node (ref "U2") (pin "14") (pinfunction "FB1_14") (pintype "passive"))
    )
    (net (code "80") (name "Net-(U2A-LX1)") (class "Default")
      (node (ref "L1") (pin "1") (pintype "passive"))
      (node (ref "U2") (pin "11") (pinfunction "LX1_11") (pintype "passive"))
    )
    (net (code "81") (name "Net-(U2B-FB2)") (class "Default")
      (node (ref "R28") (pin "1") (pinfunction "1_1") (pintype "passive"))
      (node (ref "R29") (pin "2") (pinfunction "2_2") (pintype "passive"))
      (node (ref "U2") (pin "3") (pinfunction "FB2_3") (pintype "passive"))
    )
    (net (code "82") (name "Net-(U2B-LX2)") (class "Default")
      (node (ref "L2") (pin "1") (pintype "passive"))
      (node (ref "U2") (pin "6") (pinfunction "LX2_6") (pintype "passive"))
    )
    (net (code "83") (name "SHIELD") (class "Default")
      (node (ref "RJ1") (pin "P10") (pinfunction "P10_P10") (pintype "passive"))
      (node (ref "RJ1") (pin "SHIELD0") (pinfunction "SHIELD0_SHIELD0") (pintype "passive"))
      (node (ref "RJ1") (pin "SHIELD1") (pinfunction "SHIELD1_SHIELD1") (pintype "passive"))
      (node (ref "RJ2") (pin "P10") (pinfunction "P10_P10") (pintype "passive"))
      (node (ref "RJ2") (pin "SHIELD0") (pinfunction "SHIELD0_SHIELD0") (pintype "passive"))
      (node (ref "RJ2") (pin "SHIELD1") (pinfunction "SHIELD1_SHIELD1") (pintype "passive"))
      (node (ref "RJ3") (pin "P10") (pinfunction "P10_P10") (pintype "passive"))
      (node (ref "RJ3") (pin "SHIELD0") (pinfunction "SHIELD0_SHIELD0") (pintype "passive"))
      (node (ref "RJ3") (pin "SHIELD1") (pinfunction "SHIELD1_SHIELD1") (pintype "passive"))
      (node (ref "RJ4") (pin "P10") (pinfunction "P10_P10") (pintype "passive"))
      (node (ref "RJ4") (pin "SHIELD0") (pinfunction "SHIELD0_SHIELD0") (pintype "passive"))
      (node (ref "RJ4") (pin "SHIELD1") (pinfunction "SHIELD1_SHIELD1") (pintype "passive"))
      (node (ref "RJ5") (pin "P10") (pinfunction "P10_P10") (pintype "passive"))
      (node (ref "RJ5") (pin "SHIELD0") (pinfunction "SHIELD0_SHIELD0") (pintype "passive"))
      (node (ref "RJ5") (pin "SHIELD1") (pinfunction "SHIELD1_SHIELD1") (pintype "passive"))
    )
    (net (code "84") (name "VCC_1V0") (class "Default")
      (node (ref "C10") (pin "2") (pinfunction "2_2") (pintype "passive"))
      (node (ref "C11") (pin "2") (pinfunction "2_2") (pintype "passive"))
      (node (ref "C28") (pin "1") (pinfunction "1_1") (pintype "passive"))
      (node (ref "C29") (pin "1") (pinfunction "1_1") (pintype "passive"))
      (node (ref "C3") (pin "2") (pinfunction "2_2") (pintype "passive"))
      (node (ref "C30") (pin "2") (pinfunction "2_2") (pintype "passive"))
      (node (ref "C4") (pin "2") (pinfunction "2_2") (pintype "passive"))
      (node (ref "C5") (pin "2") (pinfunction "2_2") (pintype "passive"))
      (node (ref "C6") (pin "2") (pinfunction "2_2") (pintype "passive"))
      (node (ref "C7") (pin "2") (pinfunction "2_2") (pintype "passive"))
      (node (ref "C8") (pin "2") (pinfunction "2_2") (pintype "passive"))
      (node (ref "C9") (pin "2") (pinfunction "2_2") (pintype "passive"))
      (node (ref "L1") (pin "2") (pinfunction "2_2") (pintype "passive"))
      (node (ref "R21") (pin "2") (pinfunction "2_2") (pintype "passive"))
      (node (ref "R24") (pin "2") (pinfunction "2_2") (pintype "passive"))
      (node (ref "R26") (pin "2") (pinfunction "2_2") (pintype "passive"))
      (node (ref "U1") (pin "101") (pinfunction "AVDDL_101") (pintype "passive"))
      (node (ref "U1") (pin "111") (pinfunction "AVDDL_111") (pintype "passive"))
      (node (ref "U1") (pin "124") (pinfunction "AVDDL_124") (pintype "passive"))
      (node (ref "U1") (pin "14") (pinfunction "AVDDL_14") (pintype "passive"))
      (node (ref "U1") (pin "21") (pinfunction "DVDDL_21") (pintype "passive"))
      (node (ref "U1") (pin "28") (pinfunction "AVDDL_28") (pintype "passive"))
      (node (ref "U1") (pin "53") (pinfunction "DVDDL_53") (pintype "passive"))
      (node (ref "U1") (pin "6") (pinfunction "AVDDL_6") (pintype "passive"))
      (node (ref "U1") (pin "71") (pinfunction "DVDDL_71") (pintype "passive"))
      (node (ref "U1") (pin "87") (pinfunction "DVDDL_87") (pintype "passive"))
    )
    (net (code "85") (name "VCC_3V3") (class "Default")
      (node (ref "C12") (pin "1") (pinfunction "1_1") (pintype "passive"))
      (node (ref "C13") (pin "1") (pinfunction "1_1") (pintype "passive"))
      (node (ref "C14") (pin "1") (pinfunction "1_1") (pintype "passive"))
      (node (ref "C15") (pin "1") (pinfunction "1_1") (pintype "passive"))
      (node (ref "C16") (pin "1") (pinfunction "1_1") (pintype "passive"))
      (node (ref "C17") (pin "1") (pinfunction "1_1") (pintype "passive"))
      (node (ref "C18") (pin "1") (pinfunction "1_1") (pintype "passive"))
      (node (ref "C19") (pin "1") (pinfunction "1_1") (pintype "passive"))
      (node (ref "C20") (pin "1") (pinfunction "1_1") (pintype "passive"))
      (node (ref "C21") (pin "1") (pinfunction "1_1") (pintype "passive"))
      (node (ref "C22") (pin "1") (pinfunction "1_1") (pintype "passive"))
      (node (ref "C23") (pin "1") (pinfunction "1_1") (pintype "passive"))
      (node (ref "C34") (pin "1") (pinfunction "1_1") (pintype "passive"))
      (node (ref "C35") (pin "1") (pinfunction "1_1") (pintype "passive"))
      (node (ref "C36") (pin "2") (pinfunction "2_2") (pintype "passive"))
      (node (ref "L2") (pin "2") (pinfunction "2_2") (pintype "passive"))
      (node (ref "R10") (pin "2") (pinfunction "2_2") (pintype "passive"))
      (node (ref "R11") (pin "2") (pinfunction "2_2") (pintype "passive"))
      (node (ref "R12") (pin "2") (pinfunction "2_2") (pintype "passive"))
      (node (ref "R14") (pin "2") (pinfunction "2_2") (pintype "passive"))
      (node (ref "R15") (pin "2") (pinfunction "2_2") (pintype "passive"))
      (node (ref "R16") (pin "2") (pinfunction "2_2") (pintype "passive"))
      (node (ref "R17") (pin "2") (pinfunction "2_2") (pintype "passive"))
      (node (ref "R18") (pin "2") (pinfunction "2_2") (pintype "passive"))
      (node (ref "R28") (pin "2") (pinfunction "2_2") (pintype "passive"))
      (node (ref "R30") (pin "1") (pinfunction "1_1") (pintype "passive"))
      (node (ref "R31") (pin "2") (pinfunction "2_2") (pintype "passive"))
      (node (ref "R32") (pin "1") (pinfunction "1_1") (pintype "passive"))
      (node (ref "R33") (pin "1") (pinfunction "1_1") (pintype "passive"))
      (node (ref "R34") (pin "1") (pinfunction "1_1") (pintype "passive"))
      (node (ref "R4") (pin "2") (pinfunction "2_2") (pintype "passive"))
      (node (ref "R5") (pin "2") (pinfunction "2_2") (pintype "passive"))
      (node (ref "R6") (pin "2") (pinfunction "2_2") (pintype "passive"))
      (node (ref "R7") (pin "2") (pinfunction "2_2") (pintype "passive"))
      (node (ref "R9") (pin "2") (pinfunction "2_2") (pintype "passive"))
      (node (ref "U1") (pin "1") (pinfunction "AVDDH_1") (pintype "passive"))
      (node (ref "U1") (pin "106") (pinfunction "AVDDH_106") (pintype "passive"))
      (node (ref "U1") (pin "11") (pinfunction "AVDDH_11") (pintype "passive"))
      (node (ref "U1") (pin "119") (pinfunction "AVDDH_119") (pintype "passive"))
      (node (ref "U1") (pin "17") (pinfunction "AVDDH_17") (pintype "passive"))
      (node (ref "U1") (pin "18") (pinfunction "DVDDIO_18") (pintype "passive"))
      (node (ref "U1") (pin "23") (pinfunction "AVDDH_23") (pintype "passive"))
      (node (ref "U1") (pin "33") (pinfunction "AVDDH_33") (pintype "passive"))
      (node (ref "U1") (pin "36") (pinfunction "AVDDH_36") (pintype "passive"))
      (node (ref "U1") (pin "39") (pinfunction "DVDDIO_2_39") (pintype "passive"))
      (node (ref "U1") (pin "54") (pinfunction "DVDDIO_2_54") (pintype "passive"))
      (node (ref "U1") (pin "55") (pinfunction "DVDDIO_1_55") (pintype "passive"))
      (node (ref "U1") (pin "69") (pinfunction "DVDDIO_1_69") (pintype "passive"))
      (node (ref "U1") (pin "70") (pinfunction "DVDDIO_70") (pintype "passive"))
      (node (ref "U1") (pin "88") (pinfunction "AVDDH_88") (pintype "passive"))
      (node (ref "U1") (pin "96") (pinfunction "AVDDH_96") (pintype "passive"))
    )
    (net (code "86") (name "VUSB") (class "Default")
      (node (ref "C31") (pin "2") (pinfunction "2_2") (pintype "passive"))
      (node (ref "U2") (pin "10") (pinfunction "VIN1_10") (pintype "power_in"))
      (node (ref "U2") (pin "16") (pinfunction "VCC_16") (pintype "power_in"))
      (node (ref "U2") (pin "19") (pinfunction "VIN3_19") (pintype "power_in"))
      (node (ref "U2") (pin "7") (pinfunction "VIN2_7") (pintype "power_in"))
      (node (ref "U2") (pin "8") (pinfunction "EN2_8") (pintype "passive"))
      (node (ref "U2") (pin "9") (pinfunction "EN1_9") (pintype "passive"))
      (node (ref "USB1") (pin "A4") (pinfunction "VBUS_A4") (pintype "passive"))
      (node (ref "USB1") (pin "A9") (pinfunction "VBUS_A9") (pintype "passive"))
      (node (ref "USB1") (pin "B4") (pinfunction "VBUS_B4") (pintype "passive"))
      (node (ref "USB1") (pin "B9") (pinfunction "VBUS_B9") (pintype "passive"))
    )
    (net (code "87") (name "unconnected-(U1-ATESTCK0-Pad117)") (class "Default")
      (node (ref "U1") (pin "117") (pinfunction "ATESTCK0_117") (pintype "passive+no_connect"))
    )
    (net (code "88") (name "unconnected-(U1-DIS_LPD{slash}BUZZER-Pad20)") (class "Default")
      (node (ref "U1") (pin "20") (pinfunction "DIS_LPD/BUZZER_20") (pintype "passive+no_connect"))
    )
    (net (code "89") (name "unconnected-(U1-INTERRUPT-Pad19)") (class "Default")
      (node (ref "U1") (pin "19") (pinfunction "INTERRUPT_19") (pintype "passive+no_connect"))
    )
    (net (code "90") (name "unconnected-(U1-RESERVED-Pad22)") (class "Default")
      (node (ref "U1") (pin "22") (pinfunction "RESERVED_22") (pintype "passive+no_connect"))
    )
    (net (code "91") (name "unconnected-(U1-RESERVED-Pad35)") (class "Default")
      (node (ref "U1") (pin "35") (pinfunction "RESERVED_35") (pintype "passive+no_connect"))
    )
    (net (code "92") (name "unconnected-(U1-RESERVED-Pad37)") (class "Default")
      (node (ref "U1") (pin "37") (pinfunction "RESERVED_37") (pintype "passive+no_connect"))
    )
    (net (code "93") (name "unconnected-(U1-RESERVED-Pad38)") (class "Default")
      (node (ref "U1") (pin "38") (pinfunction "RESERVED_38") (pintype "passive+no_connect"))
    )
    (net (code "94") (name "unconnected-(U1-RESERVED-Pad40)") (class "Default")
      (node (ref "U1") (pin "40") (pinfunction "RESERVED_40") (pintype "passive+no_connect"))
    )
    (net (code "95") (name "unconnected-(U1-RG1_TXCLK{slash}M1M_TXCLK{slash}M1P_RXCLK-Pad62)") (class "Default")
      (node (ref "U1") (pin "62") (pinfunction "RG1_TXCLK/M1M_TXCLK/M1P_RXCLK_62") (pintype "passive+no_connect"))
    )
    (net (code "96") (name "unconnected-(U1-RG1_TXCTL{slash}M1M_TXEN{slash}M1P_RXDV-Pad61)") (class "Default")
      (node (ref "U1") (pin "61") (pinfunction "RG1_TXCTL/M1M_TXEN/M1P_RXDV_61") (pintype "passive+no_connect"))
    )
    (net (code "97") (name "unconnected-(U1-RG1_TXD0{slash}M1M_TXD0{slash}M1P_RXD0-Pad60)") (class "Default")
      (node (ref "U1") (pin "60") (pinfunction "RG1_TXD0/M1M_TXD0/M1P_RXD0_60") (pintype "passive+no_connect"))
    )
    (net (code "98") (name "unconnected-(U1-RG1_TXD1{slash}M1M_TXD1{slash}M1P_RXD1-Pad59)") (class "Default")
      (node (ref "U1") (pin "59") (pinfunction "RG1_TXD1/M1M_TXD1/M1P_RXD1_59") (pintype "passive+no_connect"))
    )
    (net (code "99") (name "unconnected-(U1-RG1_TXD2{slash}M1M_TXD2{slash}M1P_RXD2-Pad58)") (class "Default")
      (node (ref "U1") (pin "58") (pinfunction "RG1_TXD2/M1M_TXD2/M1P_RXD2_58") (pintype "passive+no_connect"))
    )
    (net (code "100") (name "unconnected-(U1-RG1_TXD3{slash}M1M_TXD3{slash}M1P_RXD3-Pad57)") (class "Default")
      (node (ref "U1") (pin "57") (pinfunction "RG1_TXD3/M1M_TXD3/M1P_RXD3_57") (pintype "passive+no_connect"))
    )
    (net (code "101") (name "unconnected-(U1-RG2_TXCTL{slash}M2M_TXEN{slash}M2P_RXDV-Pad45)") (class "Default")
      (node (ref "U1") (pin "45") (pinfunction "RG2_TXCTL/M2M_TXEN/M2P_RXDV_45") (pintype "passive+no_connect"))
    )
    (net (code "102") (name "unconnected-(U1-RG2_TXD0{slash}M2M_TXD0{slash}M2P_RXD0-Pad44)") (class "Default")
      (node (ref "U1") (pin "44") (pinfunction "RG2_TXD0/M2M_TXD0/M2P_RXD0_44") (pintype "passive+no_connect"))
    )
    (net (code "103") (name "unconnected-(U1-RG2_TXD1{slash}M2M_TXD1{slash}M2P_RXD1-Pad43)") (class "Default")
      (node (ref "U1") (pin "43") (pinfunction "RG2_TXD1/M2M_TXD1/M2P_RXD1_43") (pintype "passive+no_connect"))
    )
    (net (code "104") (name "unconnected-(U1-RG2_TXD2{slash}M2M_TXD2{slash}M2P_RXD2-Pad42)") (class "Default")
      (node (ref "U1") (pin "42") (pinfunction "RG2_TXD2/M2M_TXD2/M2P_RXD2_42") (pintype "passive+no_connect"))
    )
    (net (code "105") (name "unconnected-(U1-RG2_TXD3{slash}M2M_TXD3{slash}M2P_RXD3-Pad41)") (class "Default")
      (node (ref "U1") (pin "41") (pinfunction "RG2_TXD3/M2M_TXD3/M2P_RXD3_41") (pintype "passive+no_connect"))
    )
    (net (code "106") (name "unconnected-(U1-RTT1-Pad15)") (class "Default")
      (node (ref "U1") (pin "15") (pinfunction "RTT1_15") (pintype "passive+no_connect"))
    )
    (net (code "107") (name "unconnected-(U1-RTT2-Pad16)") (class "Default")
      (node (ref "U1") (pin "16") (pinfunction "RTT2_16") (pintype "passive+no_connect"))
    )
    (net (code "108") (name "unconnected-(U1-SPIS_CK{slash}SCK-Pad93)") (class "Default")
      (node (ref "U1") (pin "93") (pinfunction "SPIS_CK/SCK_93") (pintype "passive+no_connect"))
    )
    (net (code "109") (name "unconnected-(U1-SPIS_CS-Pad92)") (class "Default")
      (node (ref "U1") (pin "92") (pinfunction "SPIS_CS_92") (pintype "passive+no_connect"))
    )
    (net (code "110") (name "unconnected-(U1-SPIS_DI{slash}SDA-Pad94)") (class "Default")
      (node (ref "U1") (pin "94") (pinfunction "SPIS_DI/SDA_94") (pintype "passive+no_connect"))
    )
    (net (code "111") (name "unconnected-(U1-SPIS_DO-Pad95)") (class "Default")
      (node (ref "U1") (pin "95") (pinfunction "SPIS_DO_95") (pintype "passive+no_connect"))
    )
    (net (code "112") (name "unconnected-(U2C-FB3-Pad2)") (class "Default")
      (node (ref "U2") (pin "2") (pinfunction "FB3_2") (pintype "passive"))
    )
    (net (code "113") (name "unconnected-(U2C-LX3-Pad20)") (class "Default")
      (node (ref "U2") (pin "20") (pinfunction "LX3_20") (pintype "passive"))
    )
    (net (code "114") (name "unconnected-(USB1-CC1-PadA5)") (class "Default")
      (node (ref "USB1") (pin "A5") (pinfunction "CC1_A5") (pintype "passive"))
    )
    (net (code "115") (name "unconnected-(USB1-CC2-PadB5)") (class "Default")
      (node (ref "USB1") (pin "B5") (pinfunction "CC2_B5") (pintype "passive"))
    )
    (net (code "116") (name "unconnected-(USB1-D+-PadA6)") (class "Default")
      (node (ref "USB1") (pin "A6") (pinfunction "D+_A6") (pintype "passive"))
    )
    (net (code "117") (name "unconnected-(USB1-D+-PadB6)") (class "Default")
      (node (ref "USB1") (pin "B6") (pinfunction "D+_B6") (pintype "passive"))
    )
    (net (code "118") (name "unconnected-(USB1-D--PadA7)") (class "Default")
      (node (ref "USB1") (pin "A7") (pinfunction "D-_A7") (pintype "passive"))
    )
    (net (code "119") (name "unconnected-(USB1-D--PadB7)") (class "Default")
      (node (ref "USB1") (pin "B7") (pinfunction "D-_B7") (pintype "passive"))
    )
    (net (code "120") (name "unconnected-(USB1-SBU1-PadA8)") (class "Default")
      (node (ref "USB1") (pin "A8") (pinfunction "SBU1_A8") (pintype "passive"))
    )
    (net (code "121") (name "unconnected-(USB1-SBU2-PadB8)") (class "Default")
      (node (ref "USB1") (pin "B8") (pinfunction "SBU2_B8") (pintype "passive"))
    )
  )
)
